# Motor.net
KiCad netlist of a schematic drawn in Altium Designer
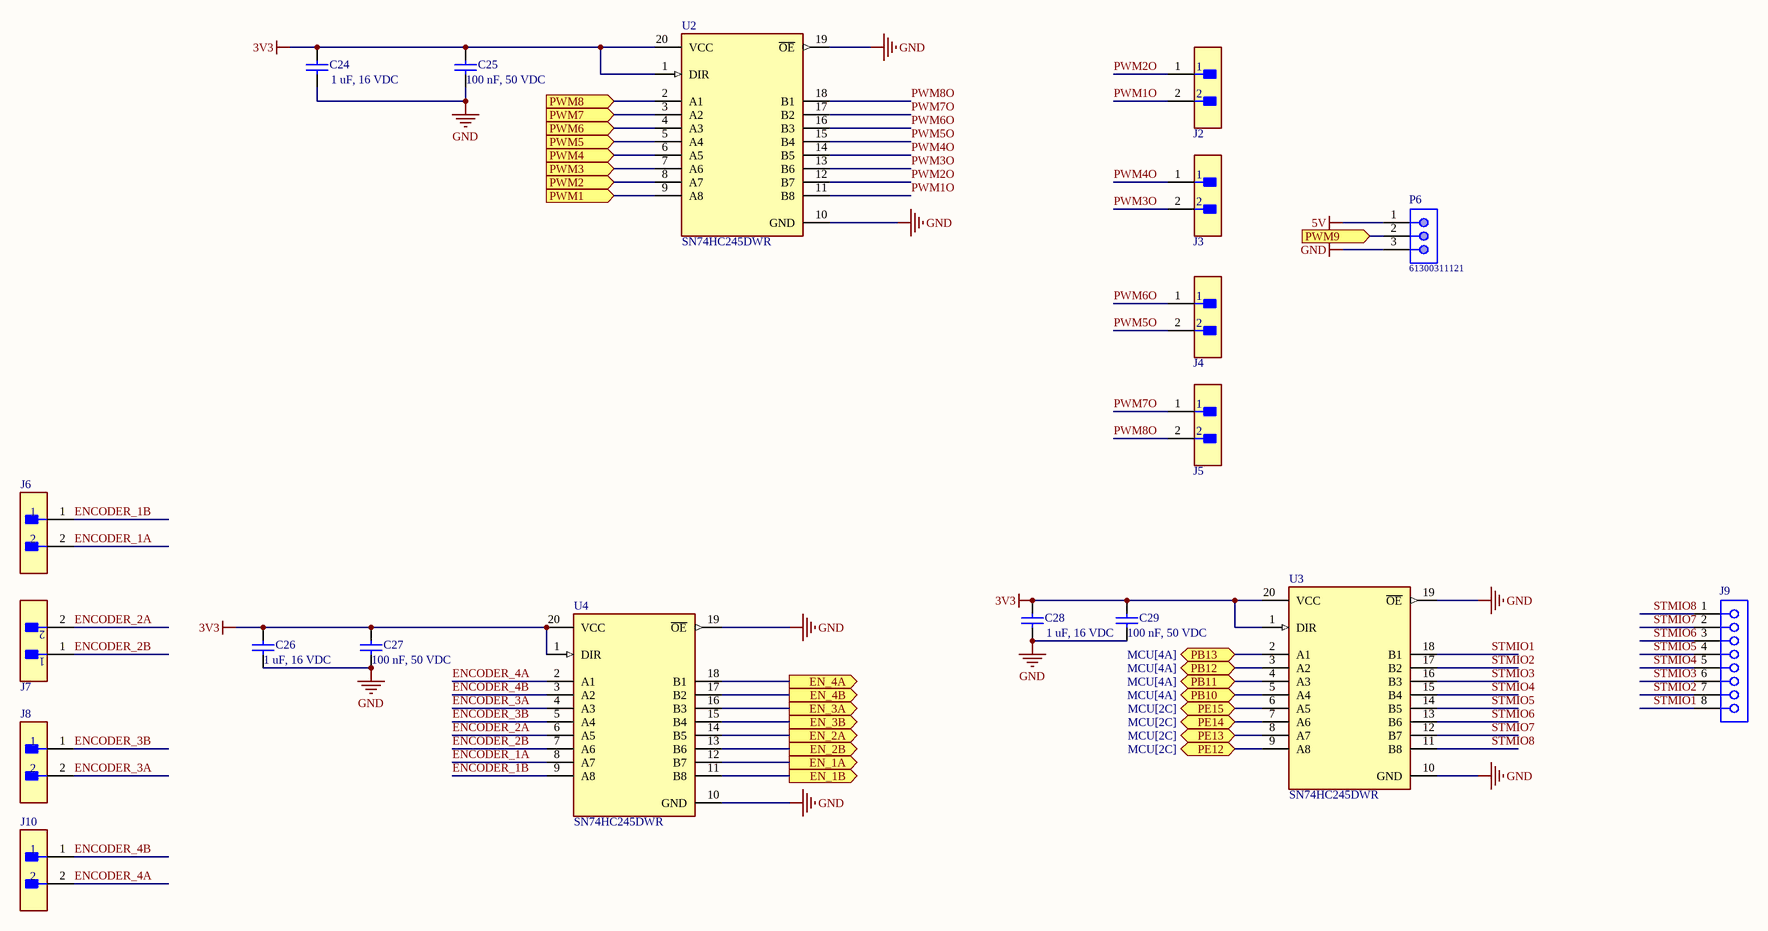
[diagram p0: Motor.SchDoc]

(export (version "E")
  (design (tool "Eeschema 10.0.6"))
  (components
    (comp (ref "C24")
      (value "1 uF, 16 VDC")
      (footprint "CAP_0603")
      (description "CAP, size 0603, 1 uF, 16 VDC")
      (fields (field (name "TOLERANCE") "+/-10%"))
      (libsource (lib "Altium_Ceramic_Cap") (part "0106031051016"))
    )
    (comp (ref "C25")
      (value "100 nF, 50 VDC")
      (footprint "CAP_0603")
      (description "CAP, size 0603, 100 nF, 50 VDC")
      (fields (field (name "TOLERANCE") "+/-10%"))
      (libsource (lib "Altium_Ceramic_Cap") (part "0106031041050"))
    )
    (comp (ref "C26")
      (value "1 uF, 16 VDC")
      (footprint "CAP_0603")
      (description "CAP, size 0603, 1 uF, 16 VDC")
      (fields (field (name "TOLERANCE") "+/-10%"))
      (libsource (lib "Altium_Ceramic_Cap") (part "0106031051016"))
    )
    (comp (ref "C27")
      (value "100 nF, 50 VDC")
      (footprint "CAP_0603")
      (description "CAP, size 0603, 100 nF, 50 VDC")
      (fields (field (name "TOLERANCE") "+/-10%"))
      (libsource (lib "Altium_Ceramic_Cap") (part "0106031041050"))
    )
    (comp (ref "C28")
      (value "1 uF, 16 VDC")
      (footprint "CAP_0603")
      (description "CAP, size 0603, 1 uF, 16 VDC")
      (fields (field (name "TOLERANCE") "+/-10%"))
      (libsource (lib "Altium_Ceramic_Cap") (part "0106031051016"))
    )
    (comp (ref "C29")
      (value "100 nF, 50 VDC")
      (footprint "CAP_0603")
      (description "CAP, size 0603, 100 nF, 50 VDC")
      (fields (field (name "TOLERANCE") "+/-10%"))
      (libsource (lib "Altium_Ceramic_Cap") (part "0106031041050"))
    )
    (comp (ref "J2")
      (value "B2B-XH-A(LF)(SN)")
      (footprint "FP-B2B-XH-A_LF_SN-MFG")
      (description "CONN HEADER VERT 2POS 2.5MM")
      (libsource (lib "Altium Content Vault") (part "3bc925449376181038e59eaffc5286c"))
    )
    (comp (ref "J3")
      (value "B2B-XH-A(LF)(SN)")
      (footprint "FP-B2B-XH-A_LF_SN-MFG")
      (description "CONN HEADER VERT 2POS 2.5MM")
      (libsource (lib "Altium Content Vault") (part "3bc925449376181038e59eaffc5286c"))
    )
    (comp (ref "J4")
      (value "B2B-XH-A(LF)(SN)")
      (footprint "FP-B2B-XH-A_LF_SN-MFG")
      (description "CONN HEADER VERT 2POS 2.5MM")
      (libsource (lib "Altium Content Vault") (part "3bc925449376181038e59eaffc5286c"))
    )
    (comp (ref "J5")
      (value "B2B-XH-A(LF)(SN)")
      (footprint "FP-B2B-XH-A_LF_SN-MFG")
      (description "CONN HEADER VERT 2POS 2.5MM")
      (libsource (lib "Altium Content Vault") (part "3bc925449376181038e59eaffc5286c"))
    )
    (comp (ref "J6")
      (value "B2B-XH-A(LF)(SN)")
      (footprint "FP-B2B-XH-A_LF_SN-MFG")
      (description "CONN HEADER VERT 2POS 2.5MM")
      (libsource (lib "") (part "3bc925449376181038e59eaffc5286c_1"))
    )
    (comp (ref "J7")
      (value "B2B-XH-A(LF)(SN)")
      (footprint "FP-B2B-XH-A_LF_SN-MFG")
      (description "CONN HEADER VERT 2POS 2.5MM")
      (libsource (lib "") (part "3bc925449376181038e59eaffc5286c_2"))
    )
    (comp (ref "J8")
      (value "B2B-XH-A(LF)(SN)")
      (footprint "FP-B2B-XH-A_LF_SN-MFG")
      (description "CONN HEADER VERT 2POS 2.5MM")
      (libsource (lib "") (part "3bc925449376181038e59eaffc5286c_1"))
    )
    (comp (ref "J9")
      (value "61300811821")
      (footprint "61300811821")
      (description "WR-PHD Socket Header, THT, pitch 2.54mm, Single Row, Vertical, 8p")
      (fields (field (name "MANUFACTURER") "Wurth Elektronik"))
      (libsource (lib "Altium_Header") (part "61300811821"))
    )
    (comp (ref "J10")
      (value "B2B-XH-A(LF)(SN)")
      (footprint "FP-B2B-XH-A_LF_SN-MFG")
      (description "CONN HEADER VERT 2POS 2.5MM")
      (libsource (lib "") (part "3bc925449376181038e59eaffc5286c_1"))
    )
    (comp (ref "P6")
      (value "61300311121")
      (footprint "61300311121")
      (description "WR-PHD Pin Header, THT, pitch 2.54mm, Single Row, Vertical, 3p")
      (fields (field (name "MANUFACTURER") "Wurth Elektronik"))
      (libsource (lib "Altium_Header") (part "61300311121"))
    )
    (comp (ref "U2")
      (value "SN74HC245DWR")
      (footprint "FP-DW0020A-IPC_A")
      (description "IC TRANSCVR NON-INVERT 6V 20SOIC")
      (libsource (lib "Altium Content Vault") (part "88901bc343d40937cf0e66f0656714f"))
    )
    (comp (ref "U3")
      (value "SN74HC245DWR")
      (footprint "FP-DW0020A-IPC_A")
      (description "IC TRANSCVR NON-INVERT 6V 20SOIC")
      (libsource (lib "Altium Content Vault") (part "88901bc343d40937cf0e66f0656714f"))
    )
    (comp (ref "U4")
      (value "SN74HC245DWR")
      (footprint "FP-DW0020A-IPC_A")
      (description "IC TRANSCVR NON-INVERT 6V 20SOIC")
      (libsource (lib "Altium Content Vault") (part "88901bc343d40937cf0e66f0656714f"))
    )
  )
  (nets
    (net (code "1") (name "/ENCODER_1A") (class "Default")
      (node (ref "J6") (pin "2") (pinfunction "2_2") (pintype "passive"))
      (node (ref "U4") (pin "8") (pinfunction "A7_8") (pintype "passive"))
    )
    (net (code "2") (name "/ENCODER_1B") (class "Default")
      (node (ref "J6") (pin "1") (pinfunction "1_1") (pintype "passive"))
      (node (ref "U4") (pin "9") (pinfunction "A8_9") (pintype "passive"))
    )
    (net (code "3") (name "/ENCODER_2A") (class "Default")
      (node (ref "J7") (pin "2") (pinfunction "2_2") (pintype "passive"))
      (node (ref "U4") (pin "6") (pinfunction "A5_6") (pintype "passive"))
    )
    (net (code "4") (name "/ENCODER_2B") (class "Default")
      (node (ref "J7") (pin "1") (pinfunction "1_1") (pintype "passive"))
      (node (ref "U4") (pin "7") (pinfunction "A6_7") (pintype "passive"))
    )
    (net (code "5") (name "/ENCODER_3A") (class "Default")
      (node (ref "J8") (pin "2") (pinfunction "2_2") (pintype "passive"))
      (node (ref "U4") (pin "4") (pinfunction "A3_4") (pintype "passive"))
    )
    (net (code "6") (name "/ENCODER_3B") (class "Default")
      (node (ref "J8") (pin "1") (pinfunction "1_1") (pintype "passive"))
      (node (ref "U4") (pin "5") (pinfunction "A4_5") (pintype "passive"))
    )
    (net (code "7") (name "/ENCODER_4A") (class "Default")
      (node (ref "J10") (pin "2") (pinfunction "2_2") (pintype "passive"))
      (node (ref "U4") (pin "2") (pinfunction "A1_2") (pintype "passive"))
    )
    (net (code "8") (name "/ENCODER_4B") (class "Default")
      (node (ref "J10") (pin "1") (pinfunction "1_1") (pintype "passive"))
      (node (ref "U4") (pin "3") (pinfunction "A2_3") (pintype "passive"))
    )
    (net (code "9") (name "/EN_1A") (class "Default")
      (node (ref "U4") (pin "12") (pinfunction "B7_12") (pintype "passive"))
    )
    (net (code "10") (name "/EN_1B") (class "Default")
      (node (ref "U4") (pin "11") (pinfunction "B8_11") (pintype "passive"))
    )
    (net (code "11") (name "/EN_2A") (class "Default")
      (node (ref "U4") (pin "14") (pinfunction "B5_14") (pintype "passive"))
    )
    (net (code "12") (name "/EN_2B") (class "Default")
      (node (ref "U4") (pin "13") (pinfunction "B6_13") (pintype "passive"))
    )
    (net (code "13") (name "/EN_3A") (class "Default")
      (node (ref "U4") (pin "16") (pinfunction "B3_16") (pintype "passive"))
    )
    (net (code "14") (name "/EN_3B") (class "Default")
      (node (ref "U4") (pin "15") (pinfunction "B4_15") (pintype "passive"))
    )
    (net (code "15") (name "/EN_4A") (class "Default")
      (node (ref "U4") (pin "18") (pinfunction "B1_18") (pintype "passive"))
    )
    (net (code "16") (name "/EN_4B") (class "Default")
      (node (ref "U4") (pin "17") (pinfunction "B2_17") (pintype "passive"))
    )
    (net (code "17") (name "/PB10") (class "Default")
      (node (ref "U3") (pin "5") (pinfunction "A4_5") (pintype "passive"))
    )
    (net (code "18") (name "/PB11") (class "Default")
      (node (ref "U3") (pin "4") (pinfunction "A3_4") (pintype "passive"))
    )
    (net (code "19") (name "/PB12") (class "Default")
      (node (ref "U3") (pin "3") (pinfunction "A2_3") (pintype "passive"))
    )
    (net (code "20") (name "/PB13") (class "Default")
      (node (ref "U3") (pin "2") (pinfunction "A1_2") (pintype "passive"))
    )
    (net (code "21") (name "/PE12") (class "Default")
      (node (ref "U3") (pin "9") (pinfunction "A8_9") (pintype "passive"))
    )
    (net (code "22") (name "/PE13") (class "Default")
      (node (ref "U3") (pin "8") (pinfunction "A7_8") (pintype "passive"))
    )
    (net (code "23") (name "/PE14") (class "Default")
      (node (ref "U3") (pin "7") (pinfunction "A6_7") (pintype "passive"))
    )
    (net (code "24") (name "/PE15") (class "Default")
      (node (ref "U3") (pin "6") (pinfunction "A5_6") (pintype "passive"))
    )
    (net (code "25") (name "/PWM1") (class "Default")
      (node (ref "U2") (pin "9") (pinfunction "A8_9") (pintype "passive"))
    )
    (net (code "26") (name "/PWM1O") (class "Default")
      (node (ref "J2") (pin "2") (pinfunction "2_2") (pintype "passive"))
      (node (ref "U2") (pin "11") (pinfunction "B8_11") (pintype "passive"))
    )
    (net (code "27") (name "/PWM2") (class "Default")
      (node (ref "U2") (pin "8") (pinfunction "A7_8") (pintype "passive"))
    )
    (net (code "28") (name "/PWM2O") (class "Default")
      (node (ref "J2") (pin "1") (pinfunction "1_1") (pintype "passive"))
      (node (ref "U2") (pin "12") (pinfunction "B7_12") (pintype "passive"))
    )
    (net (code "29") (name "/PWM3") (class "Default")
      (node (ref "U2") (pin "7") (pinfunction "A6_7") (pintype "passive"))
    )
    (net (code "30") (name "/PWM3O") (class "Default")
      (node (ref "J3") (pin "2") (pinfunction "2_2") (pintype "passive"))
      (node (ref "U2") (pin "13") (pinfunction "B6_13") (pintype "passive"))
    )
    (net (code "31") (name "/PWM4") (class "Default")
      (node (ref "U2") (pin "6") (pinfunction "A5_6") (pintype "passive"))
    )
    (net (code "32") (name "/PWM4O") (class "Default")
      (node (ref "J3") (pin "1") (pinfunction "1_1") (pintype "passive"))
      (node (ref "U2") (pin "14") (pinfunction "B5_14") (pintype "passive"))
    )
    (net (code "33") (name "/PWM5") (class "Default")
      (node (ref "U2") (pin "5") (pinfunction "A4_5") (pintype "passive"))
    )
    (net (code "34") (name "/PWM5O") (class "Default")
      (node (ref "J4") (pin "2") (pinfunction "2_2") (pintype "passive"))
      (node (ref "U2") (pin "15") (pinfunction "B4_15") (pintype "passive"))
    )
    (net (code "35") (name "/PWM6") (class "Default")
      (node (ref "U2") (pin "4") (pinfunction "A3_4") (pintype "passive"))
    )
    (net (code "36") (name "/PWM6O") (class "Default")
      (node (ref "J4") (pin "1") (pinfunction "1_1") (pintype "passive"))
      (node (ref "U2") (pin "16") (pinfunction "B3_16") (pintype "passive"))
    )
    (net (code "37") (name "/PWM7") (class "Default")
      (node (ref "U2") (pin "3") (pinfunction "A2_3") (pintype "passive"))
    )
    (net (code "38") (name "/PWM7O") (class "Default")
      (node (ref "J5") (pin "1") (pinfunction "1_1") (pintype "passive"))
      (node (ref "U2") (pin "17") (pinfunction "B2_17") (pintype "passive"))
    )
    (net (code "39") (name "/PWM8") (class "Default")
      (node (ref "U2") (pin "2") (pinfunction "A1_2") (pintype "passive"))
    )
    (net (code "40") (name "/PWM8O") (class "Default")
      (node (ref "J5") (pin "2") (pinfunction "2_2") (pintype "passive"))
      (node (ref "U2") (pin "18") (pinfunction "B1_18") (pintype "passive"))
    )
    (net (code "41") (name "/PWM9") (class "Default")
      (node (ref "P6") (pin "2") (pinfunction "2_2") (pintype "passive"))
    )
    (net (code "42") (name "/STMIO1") (class "Default")
      (node (ref "J9") (pin "8") (pinfunction "8_8") (pintype "passive"))
      (node (ref "U3") (pin "18") (pinfunction "B1_18") (pintype "passive"))
    )
    (net (code "43") (name "/STMIO2") (class "Default")
      (node (ref "J9") (pin "7") (pinfunction "7_7") (pintype "passive"))
      (node (ref "U3") (pin "17") (pinfunction "B2_17") (pintype "passive"))
    )
    (net (code "44") (name "/STMIO3") (class "Default")
      (node (ref "J9") (pin "6") (pinfunction "6_6") (pintype "passive"))
      (node (ref "U3") (pin "16") (pinfunction "B3_16") (pintype "passive"))
    )
    (net (code "45") (name "/STMIO4") (class "Default")
      (node (ref "J9") (pin "5") (pinfunction "5_5") (pintype "passive"))
      (node (ref "U3") (pin "15") (pinfunction "B4_15") (pintype "passive"))
    )
    (net (code "46") (name "/STMIO5") (class "Default")
      (node (ref "J9") (pin "4") (pinfunction "4_4") (pintype "passive"))
      (node (ref "U3") (pin "14") (pinfunction "B5_14") (pintype "passive"))
    )
    (net (code "47") (name "/STMIO6") (class "Default")
      (node (ref "J9") (pin "3") (pinfunction "3_3") (pintype "passive"))
      (node (ref "U3") (pin "13") (pinfunction "B6_13") (pintype "passive"))
    )
    (net (code "48") (name "/STMIO7") (class "Default")
      (node (ref "J9") (pin "2") (pinfunction "2_2") (pintype "passive"))
      (node (ref "U3") (pin "12") (pinfunction "B7_12") (pintype "passive"))
    )
    (net (code "49") (name "/STMIO8") (class "Default")
      (node (ref "J9") (pin "1") (pinfunction "1_1") (pintype "passive"))
      (node (ref "U3") (pin "11") (pinfunction "B8_11") (pintype "passive"))
    )
    (net (code "50") (name "3V3") (class "Default")
      (node (ref "C24") (pin "2") (pinfunction "2_2") (pintype "passive"))
      (node (ref "C25") (pin "2") (pinfunction "2_2") (pintype "passive"))
      (node (ref "C26") (pin "2") (pinfunction "2_2") (pintype "passive"))
      (node (ref "C27") (pin "2") (pinfunction "2_2") (pintype "passive"))
      (node (ref "C28") (pin "2") (pinfunction "2_2") (pintype "passive"))
      (node (ref "C29") (pin "2") (pinfunction "2_2") (pintype "passive"))
      (node (ref "U2") (pin "1") (pinfunction "DIR_1") (pintype "input"))
      (node (ref "U2") (pin "20") (pinfunction "VCC_20") (pintype "open_emitter"))
      (node (ref "U3") (pin "1") (pinfunction "DIR_1") (pintype "input"))
      (node (ref "U3") (pin "20") (pinfunction "VCC_20") (pintype "open_emitter"))
      (node (ref "U4") (pin "1") (pinfunction "DIR_1") (pintype "input"))
      (node (ref "U4") (pin "20") (pinfunction "VCC_20") (pintype "open_emitter"))
    )
    (net (code "51") (name "5V") (class "Default")
      (node (ref "P6") (pin "1") (pinfunction "1_1") (pintype "passive"))
    )
    (net (code "52") (name "GND") (class "Default")
      (node (ref "C24") (pin "1") (pinfunction "1_1") (pintype "passive"))
      (node (ref "C25") (pin "1") (pinfunction "1_1") (pintype "passive"))
      (node (ref "C26") (pin "1") (pinfunction "1_1") (pintype "passive"))
      (node (ref "C27") (pin "1") (pinfunction "1_1") (pintype "passive"))
      (node (ref "C28") (pin "1") (pinfunction "1_1") (pintype "passive"))
      (node (ref "C29") (pin "1") (pinfunction "1_1") (pintype "passive"))
      (node (ref "P6") (pin "3") (pinfunction "3_3") (pintype "passive"))
      (node (ref "U2") (pin "10") (pinfunction "GND_10") (pintype "power_in"))
      (node (ref "U2") (pin "19") (pinfunction "~{OE}_19") (pintype "output"))
      (node (ref "U3") (pin "10") (pinfunction "GND_10") (pintype "power_in"))
      (node (ref "U3") (pin "19") (pinfunction "~{OE}_19") (pintype "output"))
      (node (ref "U4") (pin "10") (pinfunction "GND_10") (pintype "power_in"))
      (node (ref "U4") (pin "19") (pinfunction "~{OE}_19") (pintype "output"))
    )
  )
)
